# Battery-Connection.net
KiCad netlist of a schematic drawn in EAGLE
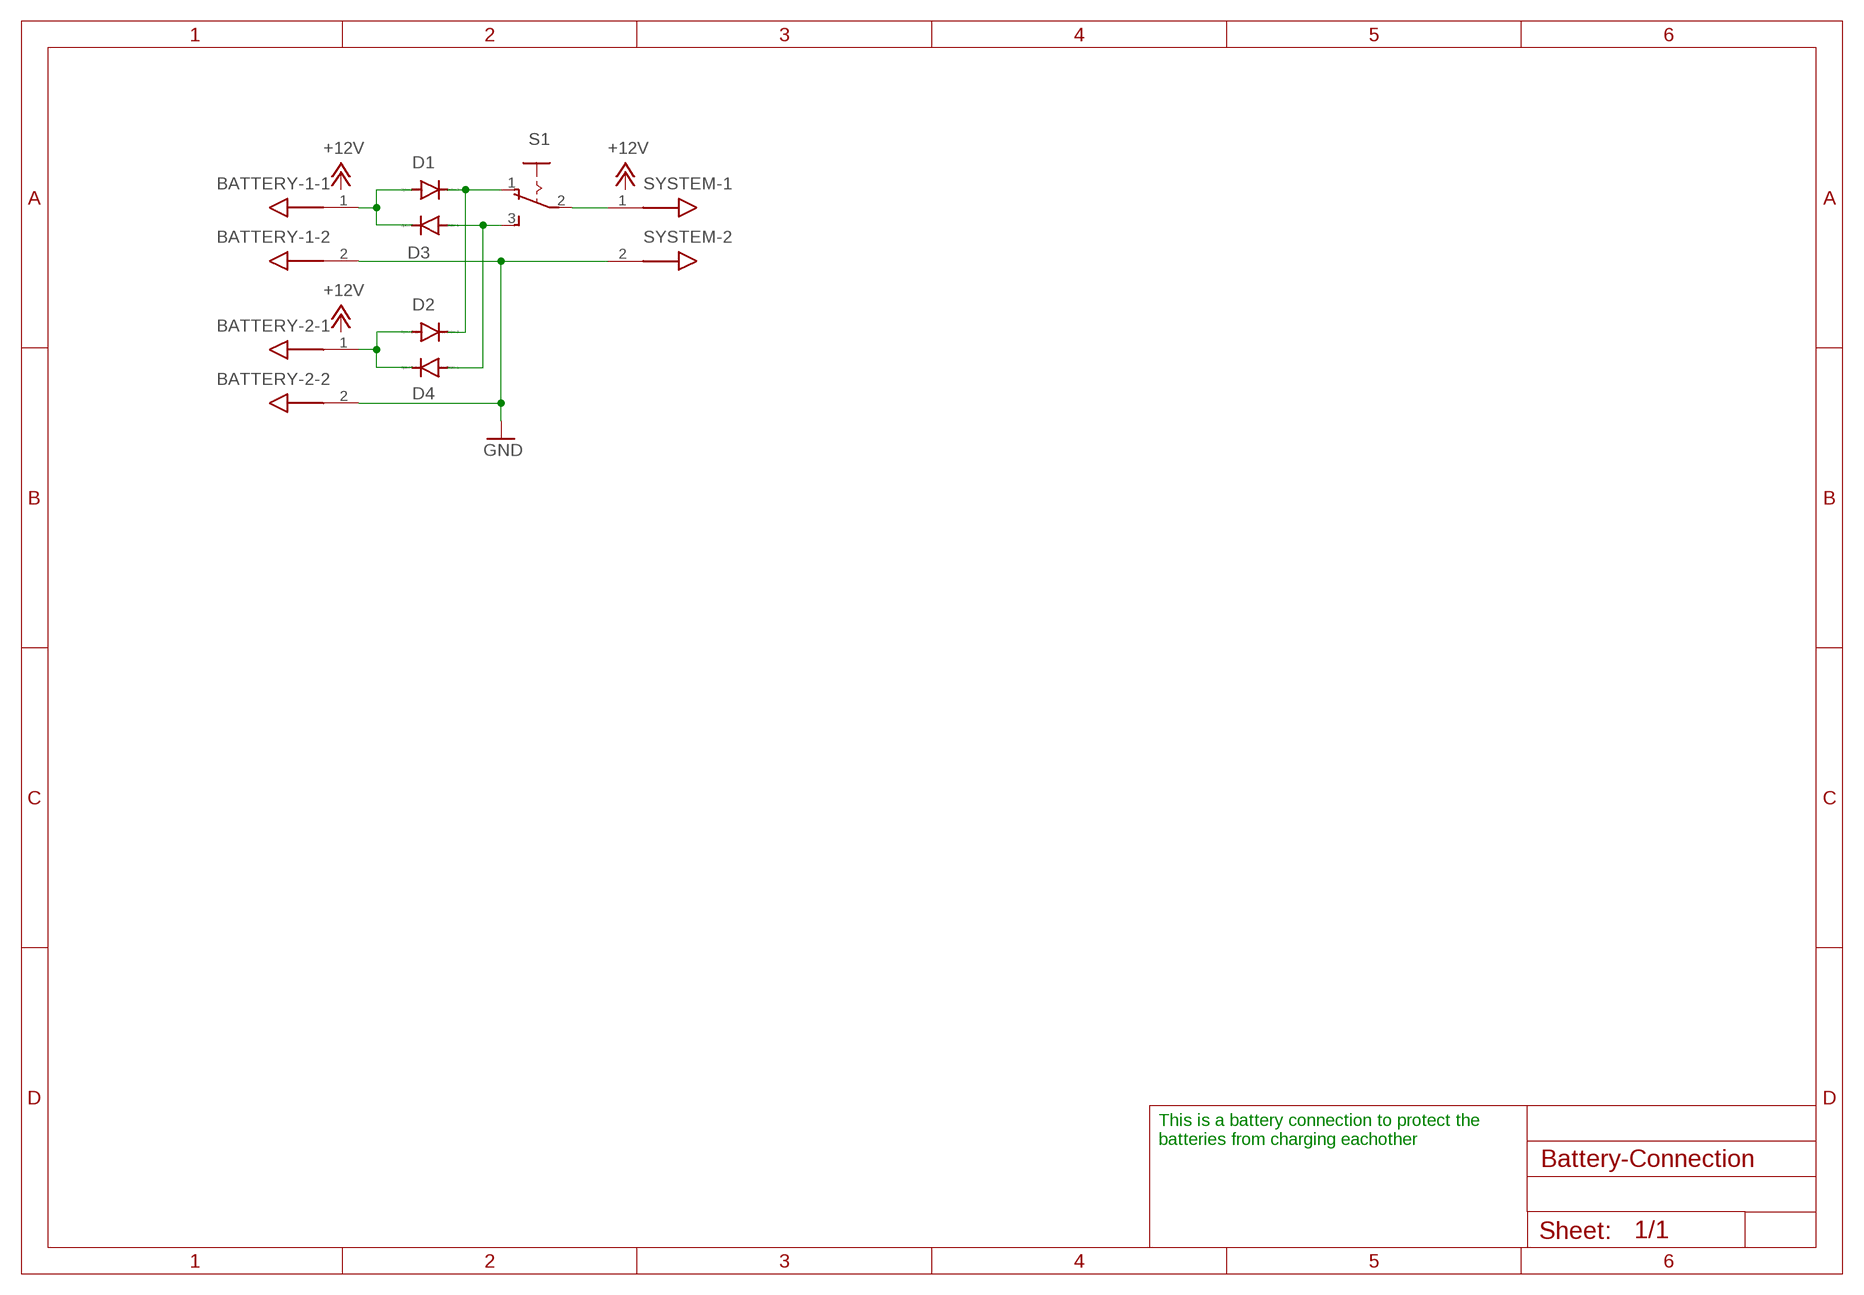
[diagram p0: schematic, sheet 1]

(export (version "E")
  (design (tool "Eeschema 10.0.6"))
  (components
    (comp (ref "BATTERY-1")
      (value "0026604020")
      (footprint "eagle-import:KK41791-4020_2-PIN")
      (fields (field (name "MANUFACTURER") "Molex Inc"))
      (libsource (lib "eagle-import") (part "0026604020"))
    )
    (comp (ref "BATTERY-2")
      (value "0026604020")
      (footprint "eagle-import:KK41791-4020_2-PIN")
      (fields (field (name "MANUFACTURER") "Molex Inc"))
      (libsource (lib "eagle-import") (part "0026604020"))
    )
    (comp (ref "D1")
      (value "1N4942")
      (footprint "eagle-import:DO41-10")
      (libsource (lib "eagle-import") (part "1N4942"))
    )
    (comp (ref "D2")
      (value "1N4942")
      (footprint "eagle-import:DO41-10")
      (libsource (lib "eagle-import") (part "1N4942"))
    )
    (comp (ref "D3")
      (value "1N4942")
      (footprint "eagle-import:DO41-10")
      (libsource (lib "eagle-import") (part "1N4942"))
    )
    (comp (ref "D4")
      (value "1N4942")
      (footprint "eagle-import:DO41-10")
      (libsource (lib "eagle-import") (part "1N4942"))
    )
    (comp (ref "S1")
      (value "255SB")
      (footprint "eagle-import:255SB")
      (libsource (lib "eagle-import") (part "255SB"))
    )
    (comp (ref "SYSTEM")
      (value "0026604020")
      (footprint "eagle-import:KK41791-4020_2-PIN")
      (fields (field (name "MANUFACTURER") "Molex Inc"))
      (libsource (lib "eagle-import") (part "0026604020"))
    )
  )
  (nets
    (net (code "2") (name "GND") (class "Default")
      (node (ref "BATTERY-1") (pin "2") (pinfunction "P$1_2") (pintype "bidirectional"))
      (node (ref "BATTERY-2") (pin "2") (pinfunction "P$1_2") (pintype "bidirectional"))
      (node (ref "SYSTEM") (pin "2") (pinfunction "P$1_2") (pintype "bidirectional"))
    )
    (net (code "3") (name "Net-(BATTERY-1A-P$1)") (class "Default")
      (node (ref "BATTERY-1") (pin "1") (pinfunction "P$1_1") (pintype "bidirectional"))
      (node (ref "D1") (pin "A") (pinfunction "A_A") (pintype "passive"))
      (node (ref "D3") (pin "C") (pinfunction "C_C") (pintype "passive"))
    )
    (net (code "4") (name "Net-(BATTERY-2A-P$1)") (class "Default")
      (node (ref "BATTERY-2") (pin "1") (pinfunction "P$1_1") (pintype "bidirectional"))
      (node (ref "D2") (pin "A") (pinfunction "A_A") (pintype "passive"))
      (node (ref "D4") (pin "C") (pinfunction "C_C") (pintype "passive"))
    )
    (net (code "5") (name "Net-(S1-O)") (class "Default")
      (node (ref "D1") (pin "C") (pinfunction "C_C") (pintype "passive"))
      (node (ref "D2") (pin "C") (pinfunction "C_C") (pintype "passive"))
      (node (ref "S1") (pin "1") (pinfunction "O_1") (pintype "passive"))
    )
    (net (code "6") (name "Net-(S1-P)") (class "Default")
      (node (ref "S1") (pin "2") (pinfunction "P_2") (pintype "passive"))
      (node (ref "SYSTEM") (pin "1") (pinfunction "P$1_1") (pintype "bidirectional"))
    )
    (net (code "7") (name "Net-(S1-S)") (class "Default")
      (node (ref "D3") (pin "A") (pinfunction "A_A") (pintype "passive"))
      (node (ref "D4") (pin "A") (pinfunction "A_A") (pintype "passive"))
      (node (ref "S1") (pin "3") (pinfunction "S_3") (pintype "passive"))
    )
  )
)
